# SCH_NFC-Business-Card_2024-03-18.net
KiCad netlist of a schematic drawn in EasyEDA
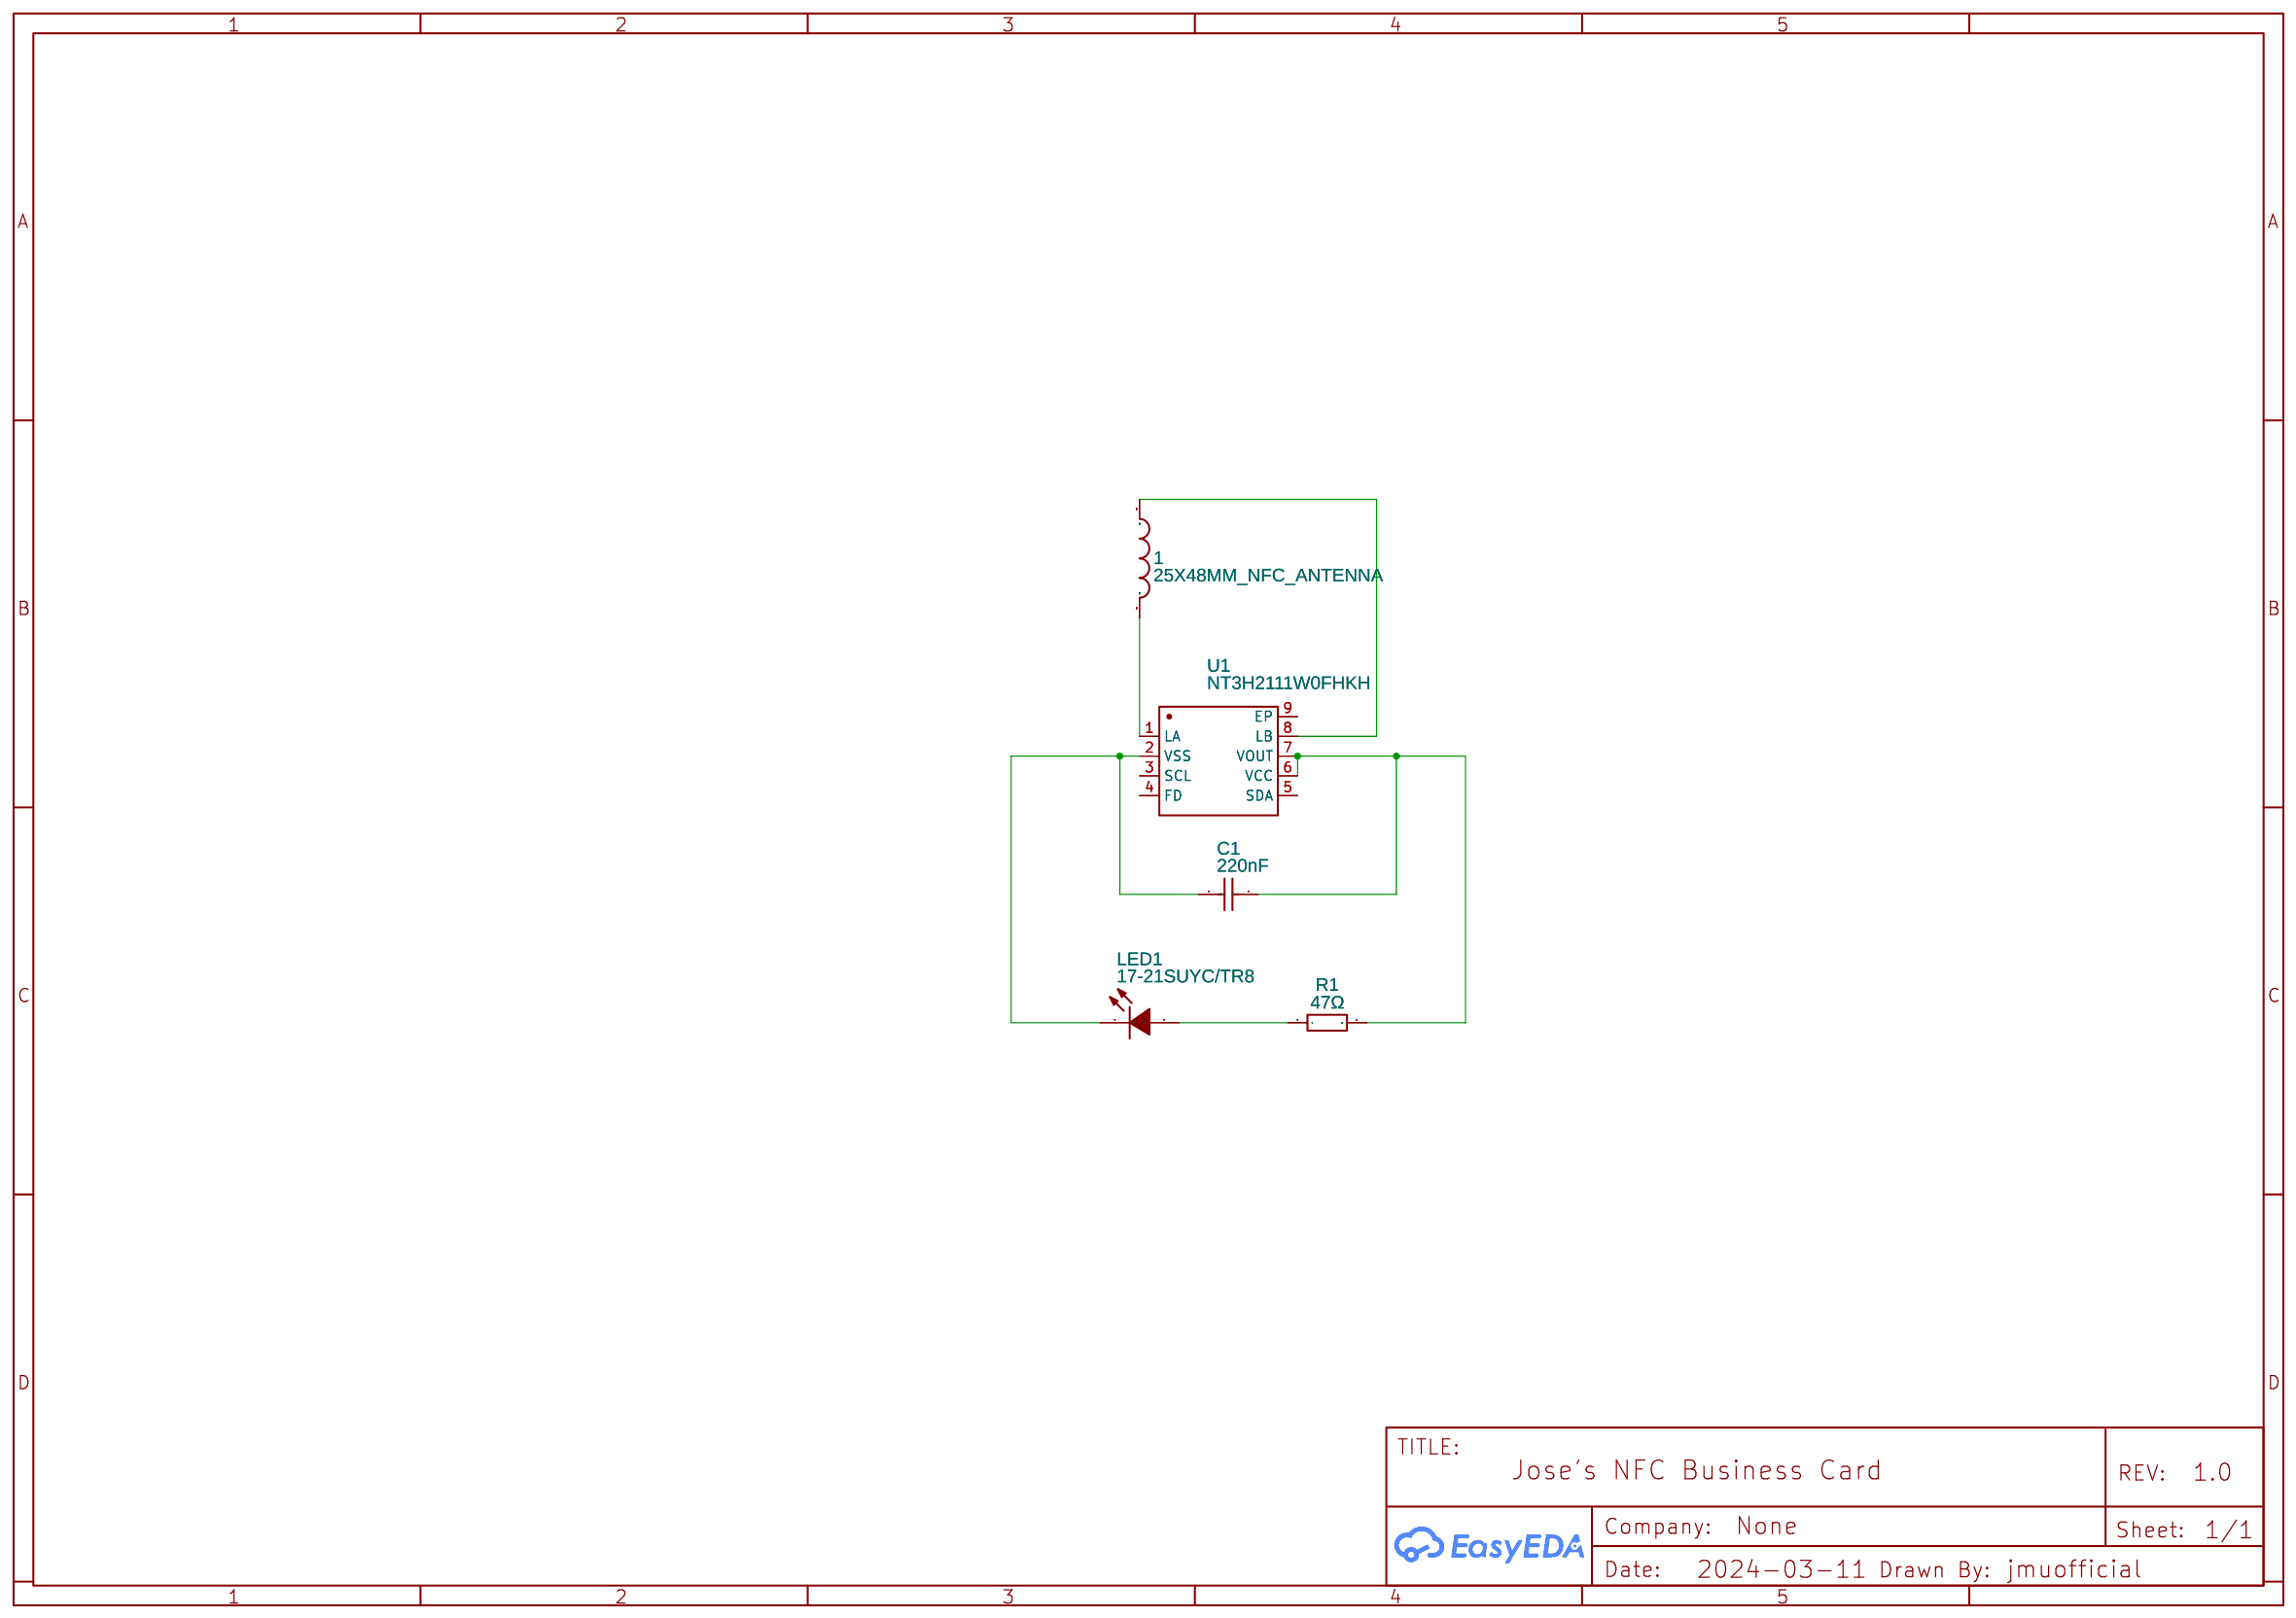
[diagram p0: schematic sheet]

(export (version "E")
  (design (tool "Eeschema 10.0.6"))
  (components
    (comp (ref "1") (value "25X48MM_NFC_ANTENNA") (libsource (lib "") (part "25X48MM_NFC_ANTENNA")))
    (comp (ref "C1")
      (value "220nF")
      (fields
        (field (name "Manufacturer Part") "CL10B224KA8NNNC")
        (field (name "Manufacturer") "SAMSUNG(三星)")
      )
      (libsource (lib "") (part "CL10B224KA8NNNC"))
    )
    (comp (ref "LED1")
      (value "17-21SUYC/TR8")
      (fields (field (name "Manufacturer Part") "KT-0805黄灯") (field (name "Manufacturer") "KENTO"))
      (libsource (lib "") (part "17-21SUYC/TR8"))
    )
    (comp (ref "R1")
      (value "47Ω")
      (fields
        (field (name "Manufacturer Part") "0603WAF470JT5E")
        (field (name "Manufacturer") "UNI-ROYAL(厚声)")
      )
      (libsource (lib "") (part "0603WAF470JT5E"))
    )
    (comp (ref "U1")
      (value "NT3H2111W0FHKH")
      (fields (field (name "Manufacturer") "NXP(恩智浦)"))
      (libsource (lib "") (part "NT3H2111W0FHKH"))
    )
  )
  (nets
    (net (code "1") (name "Net-(LED1-+)") (class "Default")
      (node (ref "LED1") (pin "1") (pinfunction "+_1") (pintype "unspecified"))
      (node (ref "R1") (pin "1") (pinfunction "1_1") (pintype "input"))
    )
    (net (code "2") (name "Net-(LED1--)") (class "Default")
      (node (ref "C1") (pin "1") (pinfunction "1_1") (pintype "input"))
      (node (ref "LED1") (pin "2") (pinfunction "-_2") (pintype "unspecified"))
      (node (ref "U1") (pin "2") (pinfunction "VSS_2") (pintype "unspecified"))
    )
    (net (code "3") (name "Net-(U1-LA)") (class "Default")
      (node (ref "1") (pin "P$2") (pinfunction "P$2_P$2") (pintype "bidirectional"))
      (node (ref "U1") (pin "1") (pinfunction "LA_1") (pintype "unspecified"))
    )
    (net (code "4") (name "Net-(U1-LB)") (class "Default")
      (node (ref "1") (pin "P$1") (pinfunction "P$1_P$1") (pintype "bidirectional"))
      (node (ref "U1") (pin "8") (pinfunction "LB_8") (pintype "unspecified"))
    )
    (net (code "5") (name "Net-(U1-VCC)") (class "Default")
      (node (ref "C1") (pin "2") (pinfunction "2_2") (pintype "input"))
      (node (ref "R1") (pin "2") (pinfunction "2_2") (pintype "input"))
      (node (ref "U1") (pin "6") (pinfunction "VCC_6") (pintype "unspecified"))
      (node (ref "U1") (pin "7") (pinfunction "VOUT_7") (pintype "unspecified"))
    )
    (net (code "6") (name "unconnected-(U1-EP-Pad9)") (class "Default")
      (node (ref "U1") (pin "9") (pinfunction "EP_9") (pintype "unspecified"))
    )
    (net (code "7") (name "unconnected-(U1-FD-Pad4)") (class "Default")
      (node (ref "U1") (pin "4") (pinfunction "FD_4") (pintype "unspecified"))
    )
    (net (code "8") (name "unconnected-(U1-SCL-Pad3)") (class "Default")
      (node (ref "U1") (pin "3") (pinfunction "SCL_3") (pintype "unspecified"))
    )
    (net (code "9") (name "unconnected-(U1-SDA-Pad5)") (class "Default")
      (node (ref "U1") (pin "5") (pinfunction "SDA_5") (pintype "unspecified"))
    )
  )
)
